# ai_breakout_oled-0_96.net
KiCad netlist of a schematic drawn in EAGLE
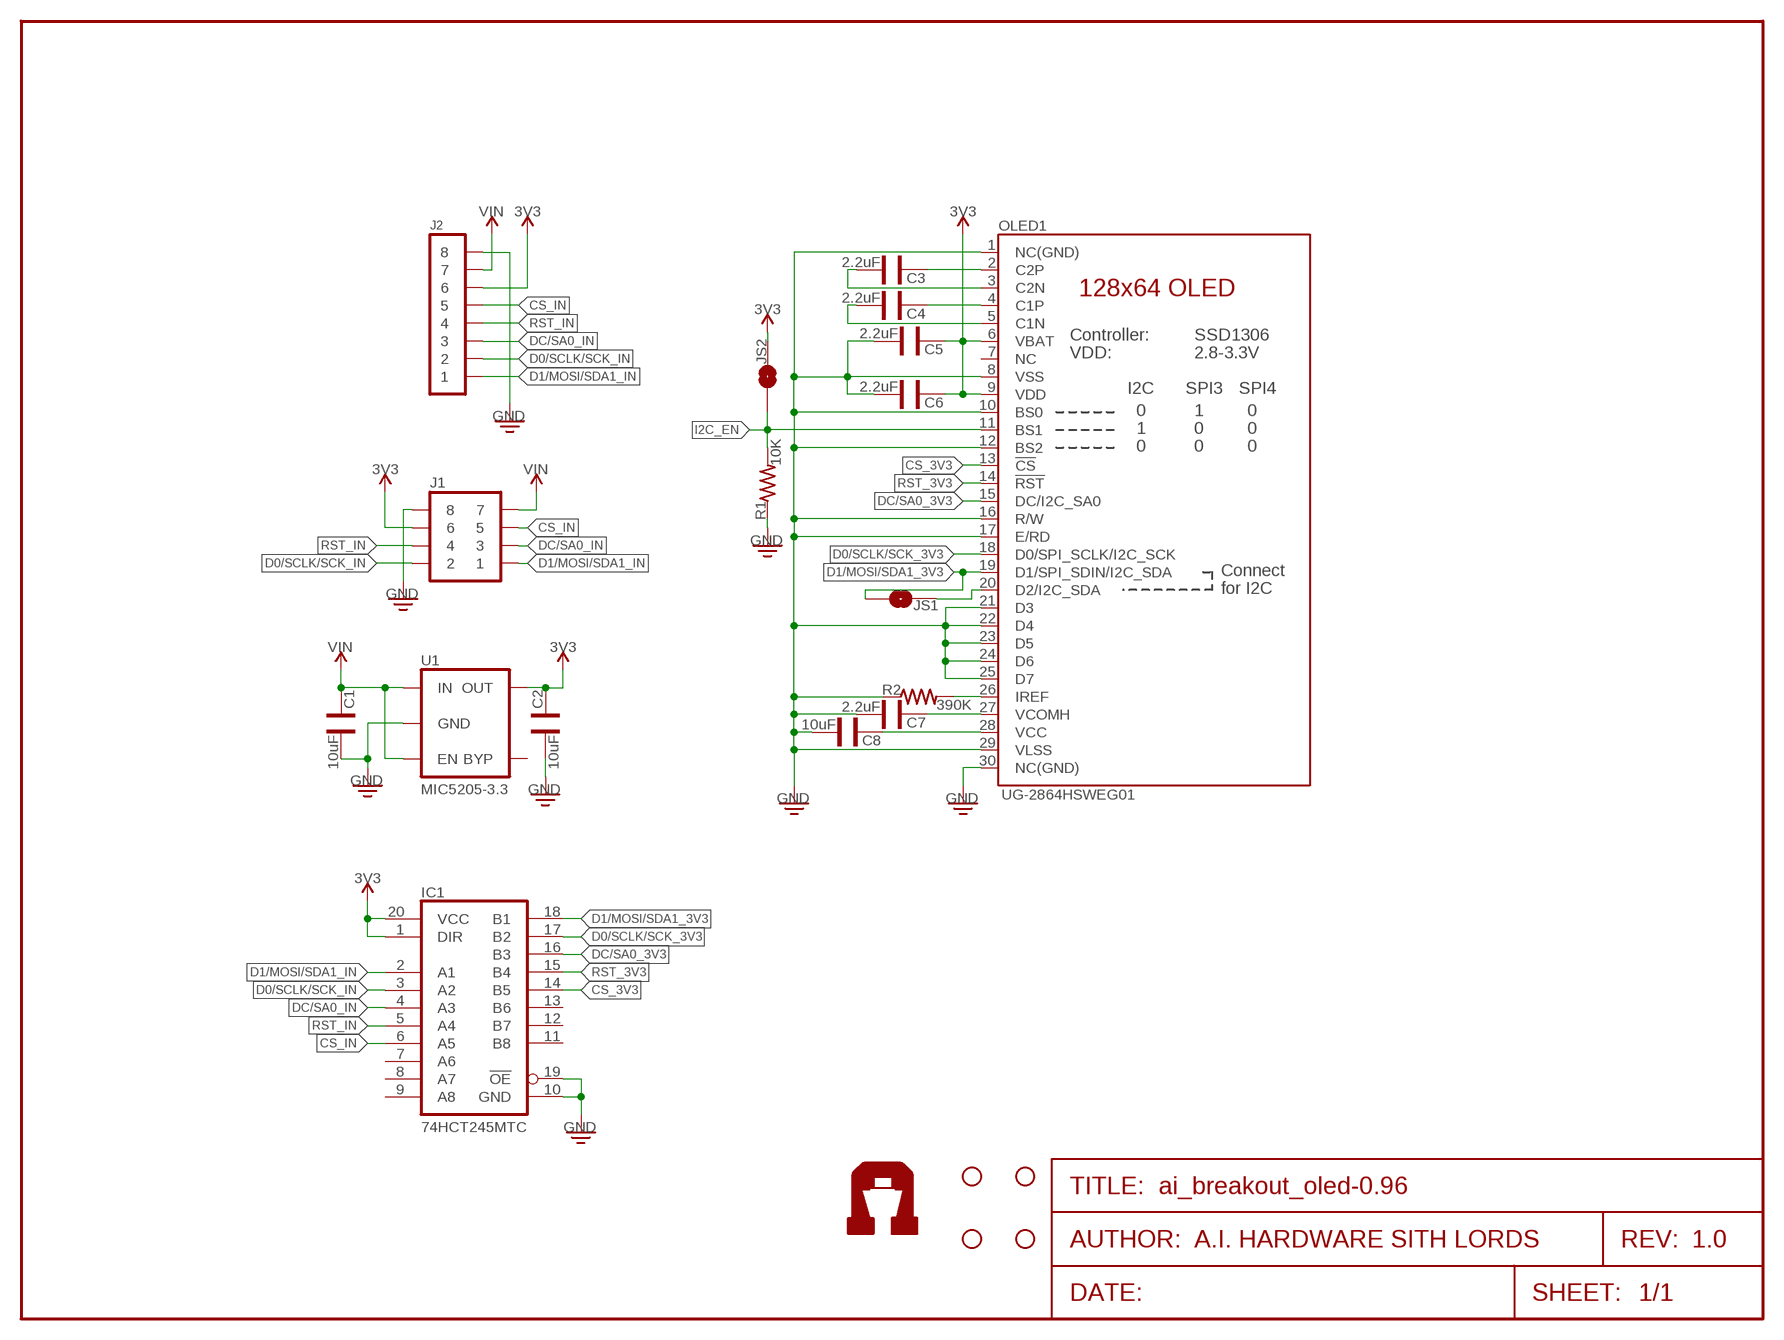
[diagram p0: schematic, sheet 1]

(export (version "E")
  (design (tool "Eeschema 10.0.6"))
  (components
    (comp (ref "C1")
      (value "10uF")
      (footprint "eagle-import:CAP-0603")
      (libsource (lib "eagle-import") (part "CAP0603"))
    )
    (comp (ref "C2")
      (value "10uF")
      (footprint "eagle-import:CAP-0603")
      (libsource (lib "eagle-import") (part "CAP0603"))
    )
    (comp (ref "C3")
      (value "2.2uF")
      (footprint "eagle-import:CAP-0603")
      (libsource (lib "eagle-import") (part "CAP0603"))
    )
    (comp (ref "C4")
      (value "2.2uF")
      (footprint "eagle-import:CAP-0603")
      (libsource (lib "eagle-import") (part "CAP0603"))
    )
    (comp (ref "C5")
      (value "2.2uF")
      (footprint "eagle-import:CAP-0603")
      (libsource (lib "eagle-import") (part "CAP0603"))
    )
    (comp (ref "C6")
      (value "2.2uF")
      (footprint "eagle-import:CAP-0603")
      (libsource (lib "eagle-import") (part "CAP0603"))
    )
    (comp (ref "C7")
      (value "2.2uF")
      (footprint "eagle-import:CAP-0603")
      (libsource (lib "eagle-import") (part "CAP0603"))
    )
    (comp (ref "C8")
      (value "10uF")
      (footprint "eagle-import:CAP-0603")
      (libsource (lib "eagle-import") (part "CAP0603"))
    )
    (comp (ref "IC1")
      (value "74HCT245MTC")
      (footprint "eagle-import:SSOP20")
      (libsource (lib "eagle-import") (part "74HCT245MTC"))
    )
    (comp (ref "J1")
      (value "2X04")
      (footprint "eagle-import:2X04")
      (libsource (lib "eagle-import") (part "2X04"))
    )
    (comp (ref "J2")
      (value "1X08")
      (footprint "eagle-import:1X08")
      (libsource (lib "eagle-import") (part "1X08"))
    )
    (comp (ref "JS1")
      (value "1X02-SJ-NO")
      (footprint "eagle-import:1X02-SJ-NO")
      (libsource (lib "eagle-import") (part "1X02-SJ-NO"))
    )
    (comp (ref "JS2")
      (value "1X02-SJ-NO")
      (footprint "eagle-import:1X02-SJ-NO")
      (libsource (lib "eagle-import") (part "1X02-SJ-NO"))
    )
    (comp (ref "M1")
      (value "STAND-OFF")
      (footprint "eagle-import:STAND-OFF")
      (libsource (lib "eagle-import") (part "STAND-OFF"))
    )
    (comp (ref "M2")
      (value "STAND-OFF")
      (footprint "eagle-import:STAND-OFF")
      (libsource (lib "eagle-import") (part "STAND-OFF"))
    )
    (comp (ref "M3")
      (value "STAND-OFF")
      (footprint "eagle-import:STAND-OFF")
      (libsource (lib "eagle-import") (part "STAND-OFF"))
    )
    (comp (ref "M4")
      (value "STAND-OFF")
      (footprint "eagle-import:STAND-OFF")
      (libsource (lib "eagle-import") (part "STAND-OFF"))
    )
    (comp (ref "OLED1")
      (value "UG-2864HSWEG01")
      (footprint "eagle-import:UG-2864HSWEG01_0.96_WRAP")
      (libsource (lib "eagle-import") (part "UG-2864HSWEG01-0.96"))
    )
    (comp (ref "R1")
      (value "10K")
      (footprint "eagle-import:RES-0603")
      (libsource (lib "eagle-import") (part "RES0603"))
    )
    (comp (ref "R2")
      (value "390K")
      (footprint "eagle-import:RES-0603")
      (libsource (lib "eagle-import") (part "RES0603"))
    )
    (comp (ref "U$15")
      (value "AI-LOGOXS")
      (footprint "eagle-import:AI-LOGO-XS")
      (libsource (lib "eagle-import") (part "AI-LOGOXS"))
    )
    (comp (ref "U$16")
      (value "AI-LOGOXS")
      (footprint "eagle-import:AI-LOGO-XS")
      (libsource (lib "eagle-import") (part "AI-LOGOXS"))
    )
    (comp (ref "U1")
      (value "MIC5205-3.3")
      (footprint "eagle-import:SOT23-5")
      (libsource (lib "eagle-import") (part "MIC5205-3.3"))
    )
  )
  (nets
    (net (code "1") (name "3V3") (class "Default")
      (node (ref "C2") (pin "2") (pinfunction "2_2") (pintype "passive"))
      (node (ref "C5") (pin "2") (pinfunction "2_2") (pintype "passive"))
      (node (ref "C6") (pin "2") (pinfunction "2_2") (pintype "passive"))
      (node (ref "IC1") (pin "1") (pinfunction "DIR_1") (pintype "input"))
      (node (ref "IC1") (pin "20") (pinfunction "VCC_20") (pintype "power_in"))
      (node (ref "J1") (pin "6") (pinfunction "6_6") (pintype "bidirectional"))
      (node (ref "J2") (pin "6") (pinfunction "6_6") (pintype "bidirectional"))
      (node (ref "JS2") (pin "2") (pinfunction "2_2") (pintype "passive"))
      (node (ref "OLED1") (pin "6") (pinfunction "VBAT_6") (pintype "input"))
      (node (ref "OLED1") (pin "9") (pinfunction "VDD_9") (pintype "power_in"))
      (node (ref "U1") (pin "5") (pinfunction "OUT_5") (pintype "passive"))
    )
    (net (code "2") (name "CS_3V3") (class "Default")
      (node (ref "IC1") (pin "14") (pinfunction "B5_14") (pintype "bidirectional"))
      (node (ref "OLED1") (pin "13") (pinfunction "~{CS}_13") (pintype "input"))
    )
    (net (code "3") (name "CS_IN") (class "Default")
      (node (ref "IC1") (pin "6") (pinfunction "A5_6") (pintype "bidirectional"))
      (node (ref "J1") (pin "5") (pinfunction "5_5") (pintype "bidirectional"))
      (node (ref "J2") (pin "5") (pinfunction "5_5") (pintype "bidirectional"))
    )
    (net (code "4") (name "D0{slash}SCLK{slash}SCK_3V3") (class "Default")
      (node (ref "IC1") (pin "17") (pinfunction "B2_17") (pintype "bidirectional"))
      (node (ref "OLED1") (pin "18") (pinfunction "D0/SPI_SCLK/I2C_SCK_18") (pintype "bidirectional"))
    )
    (net (code "5") (name "D0{slash}SCLK{slash}SCK_IN") (class "Default")
      (node (ref "IC1") (pin "3") (pinfunction "A2_3") (pintype "bidirectional"))
      (node (ref "J1") (pin "2") (pinfunction "2_2") (pintype "bidirectional"))
      (node (ref "J2") (pin "2") (pinfunction "2_2") (pintype "bidirectional"))
    )
    (net (code "6") (name "D1{slash}MOSI{slash}SDA1_3V3") (class "Default")
      (node (ref "IC1") (pin "18") (pinfunction "B1_18") (pintype "bidirectional"))
      (node (ref "JS1") (pin "1") (pinfunction "1_1") (pintype "passive"))
      (node (ref "OLED1") (pin "19") (pinfunction "D1/SPI_SDIN/I2C_SDA_19") (pintype "bidirectional"))
    )
    (net (code "7") (name "D1{slash}MOSI{slash}SDA1_IN") (class "Default")
      (node (ref "IC1") (pin "2") (pinfunction "A1_2") (pintype "bidirectional"))
      (node (ref "J1") (pin "1") (pinfunction "1_1") (pintype "bidirectional"))
      (node (ref "J2") (pin "1") (pinfunction "1_1") (pintype "bidirectional"))
    )
    (net (code "8") (name "DC{slash}SA0_3V3") (class "Default")
      (node (ref "IC1") (pin "16") (pinfunction "B3_16") (pintype "bidirectional"))
      (node (ref "OLED1") (pin "15") (pinfunction "DC/I2C_SA0_15") (pintype "input"))
    )
    (net (code "9") (name "DC{slash}SA0_IN") (class "Default")
      (node (ref "IC1") (pin "4") (pinfunction "A3_4") (pintype "bidirectional"))
      (node (ref "J1") (pin "3") (pinfunction "3_3") (pintype "bidirectional"))
      (node (ref "J2") (pin "3") (pinfunction "3_3") (pintype "bidirectional"))
    )
    (net (code "10") (name "GND") (class "Default")
      (node (ref "C1") (pin "1") (pinfunction "1_1") (pintype "passive"))
      (node (ref "C2") (pin "1") (pinfunction "1_1") (pintype "passive"))
      (node (ref "C5") (pin "1") (pinfunction "1_1") (pintype "passive"))
      (node (ref "C6") (pin "1") (pinfunction "1_1") (pintype "passive"))
      (node (ref "C7") (pin "1") (pinfunction "1_1") (pintype "passive"))
      (node (ref "C8") (pin "1") (pinfunction "1_1") (pintype "passive"))
      (node (ref "IC1") (pin "10") (pinfunction "GND_10") (pintype "power_in"))
      (node (ref "IC1") (pin "19") (pinfunction "~{OE}_19") (pintype "input"))
      (node (ref "J1") (pin "8") (pinfunction "8_8") (pintype "bidirectional"))
      (node (ref "J2") (pin "8") (pinfunction "8_8") (pintype "bidirectional"))
      (node (ref "OLED1") (pin "1") (pinfunction "NC(GND)_1") (pintype "input"))
      (node (ref "OLED1") (pin "10") (pinfunction "BS0_10") (pintype "input"))
      (node (ref "OLED1") (pin "12") (pinfunction "BS2_12") (pintype "input"))
      (node (ref "OLED1") (pin "16") (pinfunction "R/W_16") (pintype "input"))
      (node (ref "OLED1") (pin "17") (pinfunction "E/RD_17") (pintype "input"))
      (node (ref "OLED1") (pin "21") (pinfunction "D3_21") (pintype "bidirectional"))
      (node (ref "OLED1") (pin "22") (pinfunction "D4_22") (pintype "bidirectional"))
      (node (ref "OLED1") (pin "23") (pinfunction "D5_23") (pintype "bidirectional"))
      (node (ref "OLED1") (pin "24") (pinfunction "D6_24") (pintype "bidirectional"))
      (node (ref "OLED1") (pin "25") (pinfunction "D7_25") (pintype "bidirectional"))
      (node (ref "OLED1") (pin "29") (pinfunction "VLSS_29") (pintype "power_in"))
      (node (ref "OLED1") (pin "30") (pinfunction "NC(GND)_30") (pintype "input"))
      (node (ref "OLED1") (pin "8") (pinfunction "VSS_8") (pintype "power_in"))
      (node (ref "R1") (pin "1") (pinfunction "1_1") (pintype "passive"))
      (node (ref "R2") (pin "1") (pinfunction "1_1") (pintype "passive"))
      (node (ref "U1") (pin "2") (pinfunction "GND_2") (pintype "input"))
    )
    (net (code "11") (name "I2C_EN") (class "Default")
      (node (ref "JS2") (pin "1") (pinfunction "1_1") (pintype "passive"))
      (node (ref "OLED1") (pin "11") (pinfunction "BS1_11") (pintype "input"))
      (node (ref "R1") (pin "2") (pinfunction "2_2") (pintype "passive"))
    )
    (net (code "12") (name "Net-(OLED1-C1N)") (class "Default")
      (node (ref "C4") (pin "1") (pinfunction "1_1") (pintype "passive"))
      (node (ref "OLED1") (pin "5") (pinfunction "C1N_5") (pintype "input"))
    )
    (net (code "13") (name "Net-(OLED1-C1P)") (class "Default")
      (node (ref "C4") (pin "2") (pinfunction "2_2") (pintype "passive"))
      (node (ref "OLED1") (pin "4") (pinfunction "C1P_4") (pintype "input"))
    )
    (net (code "14") (name "Net-(OLED1-C2N)") (class "Default")
      (node (ref "C3") (pin "1") (pinfunction "1_1") (pintype "passive"))
      (node (ref "OLED1") (pin "3") (pinfunction "C2N_3") (pintype "input"))
    )
    (net (code "15") (name "Net-(OLED1-C2P)") (class "Default")
      (node (ref "C3") (pin "2") (pinfunction "2_2") (pintype "passive"))
      (node (ref "OLED1") (pin "2") (pinfunction "C2P_2") (pintype "input"))
    )
    (net (code "16") (name "Net-(OLED1-D2{slash}I2C_SDA)") (class "Default")
      (node (ref "JS1") (pin "2") (pinfunction "2_2") (pintype "passive"))
      (node (ref "OLED1") (pin "20") (pinfunction "D2/I2C_SDA_20") (pintype "bidirectional"))
    )
    (net (code "17") (name "Net-(OLED1-IREF)") (class "Default")
      (node (ref "OLED1") (pin "26") (pinfunction "IREF_26") (pintype "input"))
      (node (ref "R2") (pin "2") (pinfunction "2_2") (pintype "passive"))
    )
    (net (code "18") (name "Net-(OLED1-VCC)") (class "Default")
      (node (ref "C8") (pin "2") (pinfunction "2_2") (pintype "passive"))
      (node (ref "OLED1") (pin "28") (pinfunction "VCC_28") (pintype "power_in"))
    )
    (net (code "19") (name "Net-(OLED1-VCOMH)") (class "Default")
      (node (ref "C7") (pin "2") (pinfunction "2_2") (pintype "passive"))
      (node (ref "OLED1") (pin "27") (pinfunction "VCOMH_27") (pintype "output"))
    )
    (net (code "20") (name "RST_3V3") (class "Default")
      (node (ref "IC1") (pin "15") (pinfunction "B4_15") (pintype "bidirectional"))
      (node (ref "OLED1") (pin "14") (pinfunction "~{RST}_14") (pintype "input"))
    )
    (net (code "21") (name "RST_IN") (class "Default")
      (node (ref "IC1") (pin "5") (pinfunction "A4_5") (pintype "bidirectional"))
      (node (ref "J1") (pin "4") (pinfunction "4_4") (pintype "bidirectional"))
      (node (ref "J2") (pin "4") (pinfunction "4_4") (pintype "bidirectional"))
    )
    (net (code "22") (name "VIN") (class "Default")
      (node (ref "C1") (pin "2") (pinfunction "2_2") (pintype "passive"))
      (node (ref "J1") (pin "7") (pinfunction "7_7") (pintype "bidirectional"))
      (node (ref "J2") (pin "7") (pinfunction "7_7") (pintype "bidirectional"))
      (node (ref "U1") (pin "1") (pinfunction "IN_1") (pintype "input"))
      (node (ref "U1") (pin "3") (pinfunction "EN_3") (pintype "input"))
    )
    (net (code "23") (name "unconnected-(IC1-A6-Pad7)") (class "Default")
      (node (ref "IC1") (pin "7") (pinfunction "A6_7") (pintype "bidirectional"))
    )
    (net (code "24") (name "unconnected-(IC1-A7-Pad8)") (class "Default")
      (node (ref "IC1") (pin "8") (pinfunction "A7_8") (pintype "bidirectional"))
    )
    (net (code "25") (name "unconnected-(IC1-A8-Pad9)") (class "Default")
      (node (ref "IC1") (pin "9") (pinfunction "A8_9") (pintype "bidirectional"))
    )
    (net (code "26") (name "unconnected-(IC1-B6-Pad13)") (class "Default")
      (node (ref "IC1") (pin "13") (pinfunction "B6_13") (pintype "bidirectional"))
    )
    (net (code "27") (name "unconnected-(IC1-B7-Pad12)") (class "Default")
      (node (ref "IC1") (pin "12") (pinfunction "B7_12") (pintype "bidirectional"))
    )
    (net (code "28") (name "unconnected-(IC1-B8-Pad11)") (class "Default")
      (node (ref "IC1") (pin "11") (pinfunction "B8_11") (pintype "bidirectional"))
    )
    (net (code "29") (name "unconnected-(OLED1-NC-Pad7)") (class "Default")
      (node (ref "OLED1") (pin "7") (pinfunction "NC_7") (pintype "no_connect"))
    )
    (net (code "30") (name "unconnected-(U1-BYP-Pad4)") (class "Default")
      (node (ref "U1") (pin "4") (pinfunction "BYP_4") (pintype "input"))
    )
  )
)
